# SPI_and_enables.net
KiCad netlist of a schematic drawn in Altium Designer
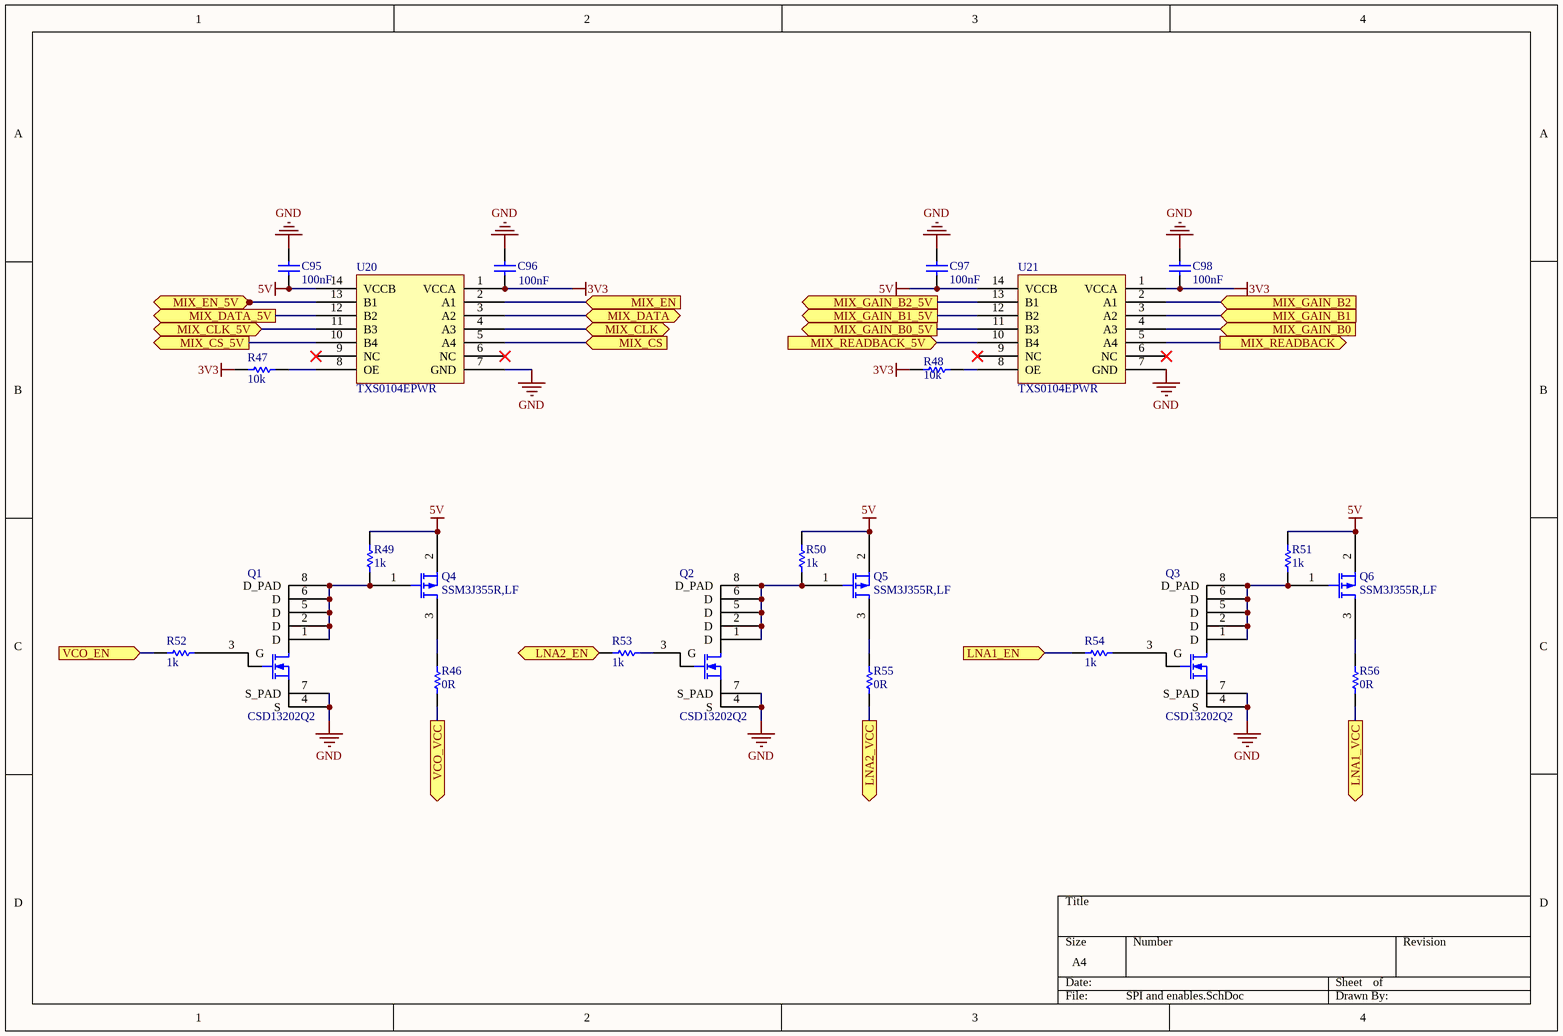
[diagram p0: SPI and enables.SchDoc]

(export (version "E")
  (design (tool "Eeschema 10.0.6"))
  (components
    (comp (ref "C95")
      (value "100nF")
      (footprint "0603 Cap")
      (description "CAP CER 16V X7R 0603")
      (fields (field (name "TOLERANCE") "10") (field (name "VOLTAGE") "16"))
      (libsource (lib "Componentes_base") (part "C_0603"))
    )
    (comp (ref "C96")
      (value "100nF")
      (footprint "0603 Cap")
      (description "CAP CER 16V X7R 0603")
      (fields (field (name "TOLERANCE") "10") (field (name "VOLTAGE") "16"))
      (libsource (lib "Componentes_base") (part "C_0603"))
    )
    (comp (ref "C97")
      (value "100nF")
      (footprint "0603 Cap")
      (description "CAP CER 16V X7R 0603")
      (fields (field (name "TOLERANCE") "10") (field (name "VOLTAGE") "16"))
      (libsource (lib "Componentes_base") (part "C_0603"))
    )
    (comp (ref "C98")
      (value "100nF")
      (footprint "0603 Cap")
      (description "CAP CER 16V X7R 0603")
      (fields (field (name "TOLERANCE") "10") (field (name "VOLTAGE") "16"))
      (libsource (lib "Componentes_base") (part "C_0603"))
    )
    (comp (ref "Q1")
      (value "CSD13202Q2")
      (footprint "8-QFN")
      (description "MOSFET N-CH 12V 76A 6SON")
      (fields (field (name "MANUFACTURER") "Texas Instruments"))
      (libsource (lib "Schlib1") (part "CSD13202Q2"))
    )
    (comp (ref "Q2")
      (value "CSD13202Q2")
      (footprint "8-QFN")
      (description "MOSFET N-CH 12V 76A 6SON")
      (fields (field (name "MANUFACTURER") "Texas Instruments"))
      (libsource (lib "Schlib1") (part "CSD13202Q2"))
    )
    (comp (ref "Q3")
      (value "CSD13202Q2")
      (footprint "8-QFN")
      (description "MOSFET N-CH 12V 76A 6SON")
      (fields (field (name "MANUFACTURER") "Texas Instruments"))
      (libsource (lib "Schlib1") (part "CSD13202Q2"))
    )
    (comp (ref "Q4")
      (value "SSM3J355R,LF")
      (footprint "SOT95P240X80-3M")
      (description "SMALL LOW ON RESISTANCE MOSFET")
      (fields (field (name "MANUFACTURER") "Toshiba Semiconductor and Storage"))
      (libsource (lib "Schlib1") (part "SSM3J355R,LF"))
    )
    (comp (ref "Q5")
      (value "SSM3J355R,LF")
      (footprint "SOT95P240X80-3M")
      (description "SMALL LOW ON RESISTANCE MOSFET")
      (fields (field (name "MANUFACTURER") "Toshiba Semiconductor and Storage"))
      (libsource (lib "Schlib1") (part "SSM3J355R,LF"))
    )
    (comp (ref "Q6")
      (value "SSM3J355R,LF")
      (footprint "SOT95P240X80-3M")
      (description "SMALL LOW ON RESISTANCE MOSFET")
      (fields (field (name "MANUFACTURER") "Toshiba Semiconductor and Storage"))
      (libsource (lib "Schlib1") (part "SSM3J355R,LF"))
    )
    (comp (ref "R46")
      (value "0R")
      (footprint "0603 Res")
      (description "SMD Resistor, 1%, 0.1W, 0603")
      (fields (field (name "TOLERANCE") "1"))
      (libsource (lib "Componentes_base") (part "R_0603"))
    )
    (comp (ref "R47")
      (value "10k")
      (footprint "0603 Res")
      (description "SMD Resistor, 1%, 0.1W, 0603")
      (fields (field (name "TOLERANCE") "1"))
      (libsource (lib "Componentes_base") (part "R_0603"))
    )
    (comp (ref "R48")
      (value "10k")
      (footprint "0603 Res")
      (description "SMD Resistor, 1%, 0.1W, 0603")
      (fields (field (name "TOLERANCE") "1"))
      (libsource (lib "Componentes_base") (part "R_0603"))
    )
    (comp (ref "R49")
      (value "1k")
      (footprint "0603 Res")
      (description "SMD Resistor, 1%, 0.1W, 0603")
      (fields (field (name "TOLERANCE") "1"))
      (libsource (lib "Componentes_base") (part "R_0603"))
    )
    (comp (ref "R50")
      (value "1k")
      (footprint "0603 Res")
      (description "SMD Resistor, 1%, 0.1W, 0603")
      (fields (field (name "TOLERANCE") "1"))
      (libsource (lib "Componentes_base") (part "R_0603"))
    )
    (comp (ref "R51")
      (value "1k")
      (footprint "0603 Res")
      (description "SMD Resistor, 1%, 0.1W, 0603")
      (fields (field (name "TOLERANCE") "1"))
      (libsource (lib "Componentes_base") (part "R_0603"))
    )
    (comp (ref "R52")
      (value "1k")
      (footprint "0603 Res")
      (description "SMD Resistor, 1%, 0.1W, 0603")
      (fields (field (name "TOLERANCE") "1"))
      (libsource (lib "Componentes_base") (part "R_0603"))
    )
    (comp (ref "R53")
      (value "1k")
      (footprint "0603 Res")
      (description "SMD Resistor, 1%, 0.1W, 0603")
      (fields (field (name "TOLERANCE") "1"))
      (libsource (lib "Componentes_base") (part "R_0603"))
    )
    (comp (ref "R54")
      (value "1k")
      (footprint "0603 Res")
      (description "SMD Resistor, 1%, 0.1W, 0603")
      (fields (field (name "TOLERANCE") "1"))
      (libsource (lib "Componentes_base") (part "R_0603"))
    )
    (comp (ref "R55")
      (value "0R")
      (footprint "0603 Res")
      (description "SMD Resistor, 1%, 0.1W, 0603")
      (fields (field (name "TOLERANCE") "1"))
      (libsource (lib "Componentes_base") (part "R_0603"))
    )
    (comp (ref "R56")
      (value "0R")
      (footprint "0603 Res")
      (description "SMD Resistor, 1%, 0.1W, 0603")
      (fields (field (name "TOLERANCE") "1"))
      (libsource (lib "Componentes_base") (part "R_0603"))
    )
    (comp (ref "U20")
      (value "TXS0104EPWR")
      (footprint "14-SOIC")
      (description "IC TRNSLTR BIDIRECTIONAL 14TSSOP")
      (fields (field (name "MANUFACTURER") "Texas Instruments") (field (name "BASE PART NUMBER") "TXS0104"))
      (libsource (lib "Schlib1") (part "TXS0104EPWR"))
    )
    (comp (ref "U21")
      (value "TXS0104EPWR")
      (footprint "14-SOIC")
      (description "IC TRNSLTR BIDIRECTIONAL 14TSSOP")
      (fields (field (name "MANUFACTURER") "Texas Instruments") (field (name "BASE PART NUMBER") "TXS0104"))
      (libsource (lib "Schlib1") (part "TXS0104EPWR"))
    )
  )
  (nets
    (net (code "1") (name "/LNA1_EN") (class "Default")
      (node (ref "R54") (pin "2") (pinfunction "2_2") (pintype "passive"))
    )
    (net (code "2") (name "/LNA1_VCC") (class "Default")
      (node (ref "R56") (pin "1") (pinfunction "1_1") (pintype "passive"))
    )
    (net (code "3") (name "/LNA2_EN") (class "Default")
      (node (ref "R53") (pin "2") (pinfunction "2_2") (pintype "passive"))
    )
    (net (code "4") (name "/LNA2_VCC") (class "Default")
      (node (ref "R55") (pin "1") (pinfunction "1_1") (pintype "passive"))
    )
    (net (code "5") (name "/MIX_CLK") (class "Default")
      (node (ref "U20") (pin "4") (pinfunction "A3_4") (pintype "passive"))
    )
    (net (code "6") (name "/MIX_CLK_5V") (class "Default")
      (node (ref "U20") (pin "11") (pinfunction "B3_11") (pintype "passive"))
    )
    (net (code "7") (name "/MIX_CS") (class "Default")
      (node (ref "U20") (pin "5") (pinfunction "A4_5") (pintype "passive"))
    )
    (net (code "8") (name "/MIX_CS_5V") (class "Default")
      (node (ref "U20") (pin "10") (pinfunction "B4_10") (pintype "passive"))
    )
    (net (code "9") (name "/MIX_DATA") (class "Default")
      (node (ref "U20") (pin "3") (pinfunction "A2_3") (pintype "passive"))
    )
    (net (code "10") (name "/MIX_DATA_5V") (class "Default")
      (node (ref "U20") (pin "12") (pinfunction "B2_12") (pintype "passive"))
    )
    (net (code "11") (name "/MIX_EN") (class "Default")
      (node (ref "U20") (pin "2") (pinfunction "A1_2") (pintype "passive"))
    )
    (net (code "12") (name "/MIX_EN_5V") (class "Default")
      (node (ref "U20") (pin "13") (pinfunction "B1_13") (pintype "passive"))
    )
    (net (code "13") (name "/MIX_GAIN_B0") (class "Default")
      (node (ref "U21") (pin "4") (pinfunction "A3_4") (pintype "passive"))
    )
    (net (code "14") (name "/MIX_GAIN_B0_5V") (class "Default")
      (node (ref "U21") (pin "11") (pinfunction "B3_11") (pintype "passive"))
    )
    (net (code "15") (name "/MIX_GAIN_B1") (class "Default")
      (node (ref "U21") (pin "3") (pinfunction "A2_3") (pintype "passive"))
    )
    (net (code "16") (name "/MIX_GAIN_B1_5V") (class "Default")
      (node (ref "U21") (pin "12") (pinfunction "B2_12") (pintype "passive"))
    )
    (net (code "17") (name "/MIX_GAIN_B2") (class "Default")
      (node (ref "U21") (pin "2") (pinfunction "A1_2") (pintype "passive"))
    )
    (net (code "18") (name "/MIX_GAIN_B2_5V") (class "Default")
      (node (ref "U21") (pin "13") (pinfunction "B1_13") (pintype "passive"))
    )
    (net (code "19") (name "/MIX_READBACK") (class "Default")
      (node (ref "U21") (pin "5") (pinfunction "A4_5") (pintype "passive"))
    )
    (net (code "20") (name "/MIX_READBACK_5V") (class "Default")
      (node (ref "U21") (pin "10") (pinfunction "B4_10") (pintype "passive"))
    )
    (net (code "21") (name "/VCO_EN") (class "Default")
      (node (ref "R52") (pin "2") (pinfunction "2_2") (pintype "passive"))
    )
    (net (code "22") (name "/VCO_VCC") (class "Default")
      (node (ref "R46") (pin "1") (pinfunction "1_1") (pintype "passive"))
    )
    (net (code "23") (name "3V3") (class "Default")
      (node (ref "C96") (pin "1") (pinfunction "1_1") (pintype "passive"))
      (node (ref "C98") (pin "1") (pinfunction "1_1") (pintype "passive"))
      (node (ref "R47") (pin "2") (pinfunction "2_2") (pintype "passive"))
      (node (ref "R48") (pin "2") (pinfunction "2_2") (pintype "passive"))
      (node (ref "U20") (pin "1") (pinfunction "VCCA_1") (pintype "passive"))
      (node (ref "U21") (pin "1") (pinfunction "VCCA_1") (pintype "passive"))
    )
    (net (code "24") (name "5V") (class "Default")
      (node (ref "C95") (pin "1") (pinfunction "1_1") (pintype "passive"))
      (node (ref "C97") (pin "1") (pinfunction "1_1") (pintype "passive"))
      (node (ref "Q4") (pin "2") (pinfunction "S_2") (pintype "passive"))
      (node (ref "Q5") (pin "2") (pinfunction "S_2") (pintype "passive"))
      (node (ref "Q6") (pin "2") (pinfunction "S_2") (pintype "passive"))
      (node (ref "R49") (pin "2") (pinfunction "2_2") (pintype "passive"))
      (node (ref "R50") (pin "2") (pinfunction "2_2") (pintype "passive"))
      (node (ref "R51") (pin "2") (pinfunction "2_2") (pintype "passive"))
      (node (ref "U20") (pin "14") (pinfunction "VCCB_14") (pintype "passive"))
      (node (ref "U21") (pin "14") (pinfunction "VCCB_14") (pintype "passive"))
    )
    (net (code "25") (name "GND") (class "Default")
      (node (ref "C95") (pin "2") (pinfunction "2_2") (pintype "passive"))
      (node (ref "C96") (pin "2") (pinfunction "2_2") (pintype "passive"))
      (node (ref "C97") (pin "2") (pinfunction "2_2") (pintype "passive"))
      (node (ref "C98") (pin "2") (pinfunction "2_2") (pintype "passive"))
      (node (ref "Q1") (pin "4") (pinfunction "S_4") (pintype "passive"))
      (node (ref "Q1") (pin "7") (pinfunction "S_PAD_7") (pintype "passive"))
      (node (ref "Q2") (pin "4") (pinfunction "S_4") (pintype "passive"))
      (node (ref "Q2") (pin "7") (pinfunction "S_PAD_7") (pintype "passive"))
      (node (ref "Q3") (pin "4") (pinfunction "S_4") (pintype "passive"))
      (node (ref "Q3") (pin "7") (pinfunction "S_PAD_7") (pintype "passive"))
      (node (ref "U20") (pin "7") (pinfunction "GND_7") (pintype "passive"))
      (node (ref "U21") (pin "7") (pinfunction "GND_7") (pintype "passive"))
    )
    (net (code "26") (name "Net-(Q1-D_PAD)") (class "Default")
      (node (ref "Q1") (pin "1") (pinfunction "D_1") (pintype "passive"))
      (node (ref "Q1") (pin "2") (pinfunction "D_2") (pintype "passive"))
      (node (ref "Q1") (pin "5") (pinfunction "D_5") (pintype "passive"))
      (node (ref "Q1") (pin "6") (pinfunction "D_6") (pintype "passive"))
      (node (ref "Q1") (pin "8") (pinfunction "D_PAD_8") (pintype "passive"))
      (node (ref "Q4") (pin "1") (pinfunction "G_1") (pintype "passive"))
      (node (ref "R49") (pin "1") (pinfunction "1_1") (pintype "passive"))
    )
    (net (code "27") (name "Net-(Q1-G)") (class "Default")
      (node (ref "Q1") (pin "3") (pinfunction "G_3") (pintype "passive"))
      (node (ref "R52") (pin "1") (pinfunction "1_1") (pintype "passive"))
    )
    (net (code "28") (name "Net-(Q2-D_PAD)") (class "Default")
      (node (ref "Q2") (pin "1") (pinfunction "D_1") (pintype "passive"))
      (node (ref "Q2") (pin "2") (pinfunction "D_2") (pintype "passive"))
      (node (ref "Q2") (pin "5") (pinfunction "D_5") (pintype "passive"))
      (node (ref "Q2") (pin "6") (pinfunction "D_6") (pintype "passive"))
      (node (ref "Q2") (pin "8") (pinfunction "D_PAD_8") (pintype "passive"))
      (node (ref "Q5") (pin "1") (pinfunction "G_1") (pintype "passive"))
      (node (ref "R50") (pin "1") (pinfunction "1_1") (pintype "passive"))
    )
    (net (code "29") (name "Net-(Q2-G)") (class "Default")
      (node (ref "Q2") (pin "3") (pinfunction "G_3") (pintype "passive"))
      (node (ref "R53") (pin "1") (pinfunction "1_1") (pintype "passive"))
    )
    (net (code "30") (name "Net-(Q3-D_PAD)") (class "Default")
      (node (ref "Q3") (pin "1") (pinfunction "D_1") (pintype "passive"))
      (node (ref "Q3") (pin "2") (pinfunction "D_2") (pintype "passive"))
      (node (ref "Q3") (pin "5") (pinfunction "D_5") (pintype "passive"))
      (node (ref "Q3") (pin "6") (pinfunction "D_6") (pintype "passive"))
      (node (ref "Q3") (pin "8") (pinfunction "D_PAD_8") (pintype "passive"))
      (node (ref "Q6") (pin "1") (pinfunction "G_1") (pintype "passive"))
      (node (ref "R51") (pin "1") (pinfunction "1_1") (pintype "passive"))
    )
    (net (code "31") (name "Net-(Q3-G)") (class "Default")
      (node (ref "Q3") (pin "3") (pinfunction "G_3") (pintype "passive"))
      (node (ref "R54") (pin "1") (pinfunction "1_1") (pintype "passive"))
    )
    (net (code "32") (name "Net-(Q4-D)") (class "Default")
      (node (ref "Q4") (pin "3") (pinfunction "D_3") (pintype "passive"))
      (node (ref "R46") (pin "2") (pinfunction "2_2") (pintype "passive"))
    )
    (net (code "33") (name "Net-(Q5-D)") (class "Default")
      (node (ref "Q5") (pin "3") (pinfunction "D_3") (pintype "passive"))
      (node (ref "R55") (pin "2") (pinfunction "2_2") (pintype "passive"))
    )
    (net (code "34") (name "Net-(Q6-D)") (class "Default")
      (node (ref "Q6") (pin "3") (pinfunction "D_3") (pintype "passive"))
      (node (ref "R56") (pin "2") (pinfunction "2_2") (pintype "passive"))
    )
    (net (code "35") (name "Net-(U20-OE)") (class "Default")
      (node (ref "R47") (pin "1") (pinfunction "1_1") (pintype "passive"))
      (node (ref "U20") (pin "8") (pinfunction "OE_8") (pintype "passive"))
    )
    (net (code "36") (name "Net-(U21-OE)") (class "Default")
      (node (ref "R48") (pin "1") (pinfunction "1_1") (pintype "passive"))
      (node (ref "U21") (pin "8") (pinfunction "OE_8") (pintype "passive"))
    )
    (net (code "37") (name "unconnected-(U20-NC-Pad6)") (class "Default")
      (node (ref "U20") (pin "6") (pinfunction "NC_6") (pintype "passive+no_connect"))
    )
    (net (code "38") (name "unconnected-(U20-NC-Pad9)") (class "Default")
      (node (ref "U20") (pin "9") (pinfunction "NC_9") (pintype "passive+no_connect"))
    )
    (net (code "39") (name "unconnected-(U21-NC-Pad6)") (class "Default")
      (node (ref "U21") (pin "6") (pinfunction "NC_6") (pintype "passive+no_connect"))
    )
    (net (code "40") (name "unconnected-(U21-NC-Pad9)") (class "Default")
      (node (ref "U21") (pin "9") (pinfunction "NC_9") (pintype "passive+no_connect"))
    )
  )
)
